# Supply.net
KiCad netlist of a schematic drawn in Altium Designer
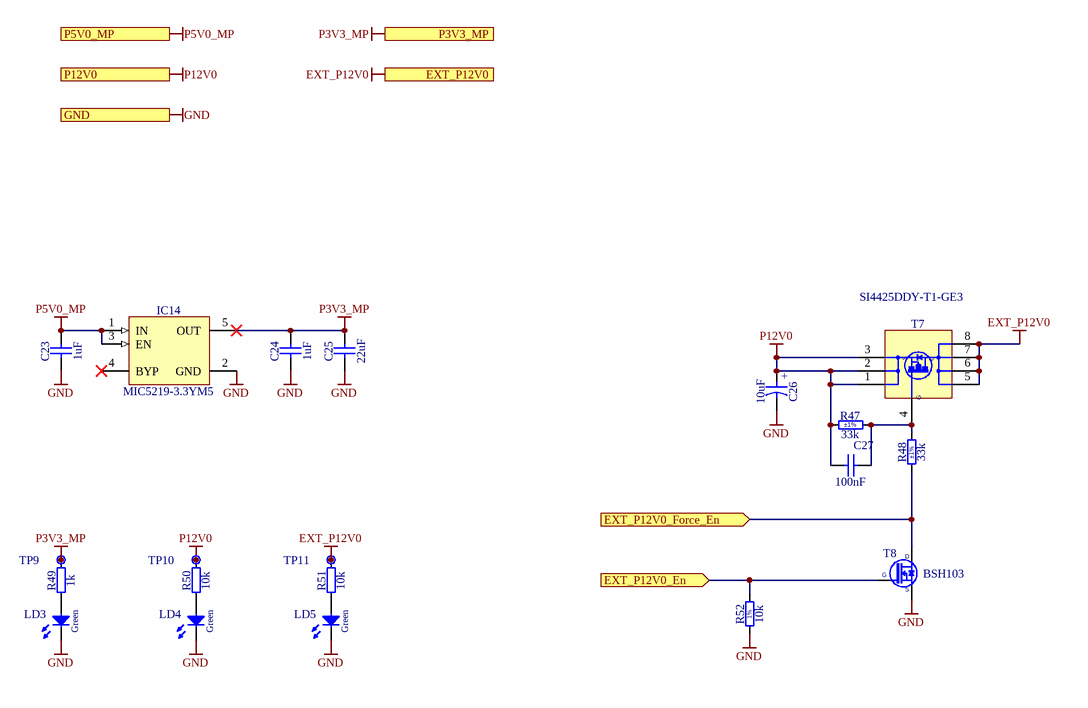
[diagram p0: Supply.SchDoc]

(export (version "E")
  (design (tool "Eeschema 10.0.6"))
  (components
    (comp (ref "C23")
      (value "1uF")
      (footprint "CAPC1608X87N")
      (description "Non-polarised capacitor")
      (fields
        (field (name "PART NUMBER") "CC0603_1UF_25V_10%_X7R")
        (field (name "VOLTAGE") "25V")
        (field (name "AUTHOR") "CERN DEM JLC")
      )
      (libsource (lib "Capacitors") (part "Capacitor - non polarized"))
    )
    (comp (ref "C24")
      (value "1uF")
      (footprint "CAPC1608X87N")
      (description "Non-polarised capacitor")
      (fields
        (field (name "PART NUMBER") "CC0603_1UF_25V_10%_X7R")
        (field (name "VOLTAGE") "25V")
        (field (name "AUTHOR") "CERN DEM JLC")
      )
      (libsource (lib "Capacitors") (part "Capacitor - non polarized"))
    )
    (comp (ref "C25")
      (value "22uF")
      (footprint "CAPC1608X90N")
      (description "Non-polarised capacitor")
      (fields
        (field (name "PART NUMBER") "CC0603_22UF_6.3V_20%_X5R")
        (field (name "VOLTAGE") "6.3V")
        (field (name "AUTHOR") "CERN DEM JLC")
      )
      (libsource (lib "Capacitors") (part "Capacitor - non polarized"))
    )
    (comp (ref "C26")
      (value "10uF")
      (footprint "CAPMP6032X280N")
      (description "Polarised capacitor")
      (fields
        (field (name "PART NUMBER") "CTE6032-28_10UF_25V_10%_LESR0500")
        (field (name "VOLTAGE") "25V")
        (field (name "AUTHOR") "CERN DEM JLC")
      )
      (libsource (lib "Capacitors") (part "Capacitor - polarized"))
    )
    (comp (ref "C27")
      (value "100nF")
      (footprint "CAPC1005X55N")
      (description "Non-polarised capacitor")
      (fields
        (field (name "PART NUMBER") "CC0402_100NF_16V_10%_X7R")
        (field (name "VOLTAGE") "16V")
        (field (name "AUTHOR") "CERN DEM JLC")
      )
      (libsource (lib "Capacitors") (part "Capacitor - non polarized"))
    )
    (comp (ref "IC14")
      (value "MIC5219-3.3YM5")
      (footprint "SOT95P280X145-5N")
      (description "500mA Peak Output LDO Regulator")
      (fields (field (name "MANUFACTURER") "MICROCHIP TECHNOLOGY") (field (name "AUTHOR") "CERN DEM WB"))
      (libsource (lib "ICs And Semiconductors") (part "MIC5219-X.XYM5"))
    )
    (comp (ref "LD3")
      (value "Green")
      (footprint "LED_KINGBRIGHT_KPH-1608CGCK")
      (description "LED Green 1C 2A")
      (fields
        (field (name "MANUFACTURER PART NUMBER") "KPH-1608CGCK")
        (field (name "PART NUMBER") "LED_KINGBRIGHT_KPH-1608CGCK")
        (field (name "AUTHOR") "CERN DEM JLC")
      )
      (libsource (lib "ICs And Semiconductors") (part "LED Green 1C 2A"))
    )
    (comp (ref "LD4")
      (value "Green")
      (footprint "LED_KINGBRIGHT_KPH-1608CGCK")
      (description "LED Green 1C 2A")
      (fields
        (field (name "MANUFACTURER PART NUMBER") "KPH-1608CGCK")
        (field (name "PART NUMBER") "LED_KINGBRIGHT_KPH-1608CGCK")
        (field (name "AUTHOR") "CERN DEM JLC")
      )
      (libsource (lib "ICs And Semiconductors") (part "LED Green 1C 2A"))
    )
    (comp (ref "LD5")
      (value "Green")
      (footprint "LED_KINGBRIGHT_KPH-1608CGCK")
      (description "LED Green 1C 2A")
      (fields
        (field (name "MANUFACTURER PART NUMBER") "KPH-1608CGCK")
        (field (name "PART NUMBER") "LED_KINGBRIGHT_KPH-1608CGCK")
        (field (name "AUTHOR") "CERN DEM JLC")
      )
      (libsource (lib "ICs And Semiconductors") (part "LED Green 1C 2A"))
    )
    (comp (ref "R47")
      (value "33k")
      (footprint "RESC1005X40N")
      (description "Resistor - 1%")
      (fields
        (field (name "TOLERANCE") "±1%")
        (field (name "PART NUMBER") "R0402_33K_1%_0.0625W_100PPM")
        (field (name "POWER") "0.0625W")
        (field (name "AUTHOR") "CERN DEM JLC")
      )
      (libsource (lib "Resistors") (part "Resistor - 1%"))
    )
    (comp (ref "R48")
      (value "33k")
      (footprint "RESC1005X40N")
      (description "Resistor - 1%")
      (fields
        (field (name "TOLERANCE") "±1%")
        (field (name "PART NUMBER") "R0402_33K_1%_0.0625W_100PPM")
        (field (name "POWER") "0.0625W")
        (field (name "AUTHOR") "CERN DEM JLC")
      )
      (libsource (lib "Resistors") (part "Resistor - 1%"))
    )
    (comp (ref "R49")
      (value "1k")
      (footprint "RESC1005X40N")
      (description "Resistor - 1%")
      (fields
        (field (name "PART NUMBER") "R0402_1K_1%_0.0625W_100PPM")
        (field (name "POWER") "0.0625W")
        (field (name "AUTHOR") "CERN DEM JLC")
      )
      (libsource (lib "Resistors") (part "Resistor - 1%"))
    )
    (comp (ref "R50")
      (value "10k")
      (footprint "RESC1005X40N")
      (description "Resistor - 1%")
      (fields
        (field (name "PART NUMBER") "R0402_10K_1%_0.0625W_100PPM")
        (field (name "POWER") "0.0625W")
        (field (name "AUTHOR") "CERN DEM JLC")
      )
      (libsource (lib "Resistors") (part "Resistor - 1%"))
    )
    (comp (ref "R51")
      (value "10k")
      (footprint "RESC1005X40N")
      (description "Resistor - 1%")
      (fields
        (field (name "PART NUMBER") "R0402_10K_1%_0.0625W_100PPM")
        (field (name "POWER") "0.0625W")
        (field (name "AUTHOR") "CERN DEM JLC")
      )
      (libsource (lib "Resistors") (part "Resistor - 1%"))
    )
    (comp (ref "R52")
      (value "10k")
      (footprint "RESC1005X40N")
      (description "Resistor - 1%")
      (fields
        (field (name "PART NUMBER") "R0402_10K_1%_0.0625W_100PPM")
        (field (name "POWER") "0.0625W")
        (field (name "AUTHOR") "CERN DEM JLC")
      )
      (libsource (lib "Resistors") (part "Resistor - 1%"))
    )
    (comp (ref "T7")
      (value "SI4425DDY-T1-GE3")
      (footprint "SOIC127P600X175-8N")
      (description "-30V -19.7A P-Channel MOSFET")
      (fields (field (name "MANUFACTURER") "VISHAY SILICONIX") (field (name "AUTHOR") "CERN DEM MR"))
      (libsource (lib "ICs And Semiconductors") (part "SI4425DDY"))
    )
    (comp (ref "T8")
      (value "BSH103")
      (footprint "SOT95P230X110-3N")
      (description "N-CHANNEL MOSFET WITH DIODE")
      (fields (field (name "MANUFACTURER") "NEXPERIA") (field (name "AUTHOR") "CERN DEM JLC"))
      (libsource (lib "ICs And Semiconductors") (part "N-MOSFET-D 1G 2S 3D"))
    )
    (comp (ref "TP9")
      (value "Test Point")
      (footprint "TPS127")
      (fields (field (name "PART NUMBER") "SMD_PAD_1.27X1.27MM") (field (name "AUTHOR") "CERN DEM JLC"))
      (libsource (lib "Eletro-mechanical") (part "Test Point"))
    )
    (comp (ref "TP10")
      (value "Test Point")
      (footprint "TPS127")
      (fields (field (name "PART NUMBER") "SMD_PAD_1.27X1.27MM") (field (name "AUTHOR") "CERN DEM JLC"))
      (libsource (lib "Eletro-mechanical") (part "Test Point"))
    )
    (comp (ref "TP11")
      (value "Test Point")
      (footprint "TPS127")
      (fields (field (name "PART NUMBER") "SMD_PAD_1.27X1.27MM") (field (name "AUTHOR") "CERN DEM JLC"))
      (libsource (lib "Eletro-mechanical") (part "Test Point"))
    )
  )
  (nets
    (net (code "1") (name "/EXT_P12V0_En") (class "Default")
      (node (ref "R52") (pin "2") (pinfunction "2_2") (pintype "passive"))
      (node (ref "T8") (pin "1") (pinfunction "G_1") (pintype "passive"))
    )
    (net (code "2") (name "/EXT_P12V0_Force_En") (class "Default")
      (node (ref "R48") (pin "1") (pinfunction "1_1") (pintype "passive"))
      (node (ref "T8") (pin "3") (pinfunction "D_3") (pintype "passive"))
    )
    (net (code "3") (name "EXT_P12V0") (class "Default")
      (node (ref "R51") (pin "2") (pinfunction "2_2") (pintype "passive"))
      (node (ref "T7") (pin "5") (pinfunction "D_5") (pintype "passive"))
      (node (ref "T7") (pin "6") (pinfunction "D_6") (pintype "passive"))
      (node (ref "T7") (pin "7") (pinfunction "D_7") (pintype "passive"))
      (node (ref "T7") (pin "8") (pinfunction "D_8") (pintype "passive"))
      (node (ref "TP11") (pin "1") (pinfunction "1_1") (pintype "bidirectional"))
    )
    (net (code "4") (name "GND") (class "Default")
      (node (ref "C23") (pin "1") (pinfunction "1_1") (pintype "passive"))
      (node (ref "C24") (pin "1") (pinfunction "1_1") (pintype "passive"))
      (node (ref "C25") (pin "1") (pinfunction "1_1") (pintype "passive"))
      (node (ref "C26") (pin "2") (pinfunction "2_2") (pintype "passive"))
      (node (ref "IC14") (pin "2") (pinfunction "GND_2") (pintype "power_in"))
      (node (ref "LD3") (pin "1") (pinfunction "C_1") (pintype "passive"))
      (node (ref "LD4") (pin "1") (pinfunction "C_1") (pintype "passive"))
      (node (ref "LD5") (pin "1") (pinfunction "C_1") (pintype "passive"))
      (node (ref "R52") (pin "1") (pinfunction "1_1") (pintype "passive"))
      (node (ref "T8") (pin "2") (pinfunction "S_2") (pintype "passive"))
    )
    (net (code "5") (name "Net-(C27-Pad2)") (class "Default")
      (node (ref "C27") (pin "2") (pinfunction "2_2") (pintype "passive"))
      (node (ref "R47") (pin "2") (pinfunction "2_2") (pintype "passive"))
      (node (ref "R48") (pin "2") (pinfunction "2_2") (pintype "passive"))
      (node (ref "T7") (pin "4") (pinfunction "S_4") (pintype "passive"))
    )
    (net (code "6") (name "Net-(LD3-A)") (class "Default")
      (node (ref "LD3") (pin "2") (pinfunction "A_2") (pintype "passive"))
      (node (ref "R49") (pin "1") (pinfunction "1_1") (pintype "passive"))
    )
    (net (code "7") (name "Net-(LD4-A)") (class "Default")
      (node (ref "LD4") (pin "2") (pinfunction "A_2") (pintype "passive"))
      (node (ref "R50") (pin "1") (pinfunction "1_1") (pintype "passive"))
    )
    (net (code "8") (name "Net-(LD5-A)") (class "Default")
      (node (ref "LD5") (pin "2") (pinfunction "A_2") (pintype "passive"))
      (node (ref "R51") (pin "1") (pinfunction "1_1") (pintype "passive"))
    )
    (net (code "9") (name "P3V3_MP") (class "Default")
      (node (ref "C24") (pin "2") (pinfunction "2_2") (pintype "passive"))
      (node (ref "C25") (pin "2") (pinfunction "2_2") (pintype "passive"))
      (node (ref "IC14") (pin "5") (pinfunction "OUT_5") (pintype "power_in"))
      (node (ref "R49") (pin "2") (pinfunction "2_2") (pintype "passive"))
      (node (ref "TP9") (pin "1") (pinfunction "1_1") (pintype "bidirectional"))
    )
    (net (code "10") (name "P5V0_MP") (class "Default")
      (node (ref "C23") (pin "2") (pinfunction "2_2") (pintype "passive"))
      (node (ref "IC14") (pin "1") (pinfunction "IN_1") (pintype "input"))
      (node (ref "IC14") (pin "3") (pinfunction "EN_3") (pintype "input"))
    )
    (net (code "11") (name "P12V0") (class "Default")
      (node (ref "C26") (pin "1") (pinfunction "1_1") (pintype "passive"))
      (node (ref "C27") (pin "1") (pinfunction "1_1") (pintype "passive"))
      (node (ref "R47") (pin "1") (pinfunction "1_1") (pintype "passive"))
      (node (ref "R50") (pin "2") (pinfunction "2_2") (pintype "passive"))
      (node (ref "T7") (pin "1") (pinfunction "S_1") (pintype "passive"))
      (node (ref "T7") (pin "2") (pinfunction "S_2") (pintype "passive"))
      (node (ref "T7") (pin "3") (pinfunction "S_3") (pintype "passive"))
      (node (ref "TP10") (pin "1") (pinfunction "1_1") (pintype "bidirectional"))
    )
    (net (code "12") (name "unconnected-(IC14-BYP-Pad4)") (class "Default")
      (node (ref "IC14") (pin "4") (pinfunction "BYP_4") (pintype "passive+no_connect"))
    )
  )
)
